# led_kocka_gornja.net
KiCad netlist of a schematic drawn in EAGLE
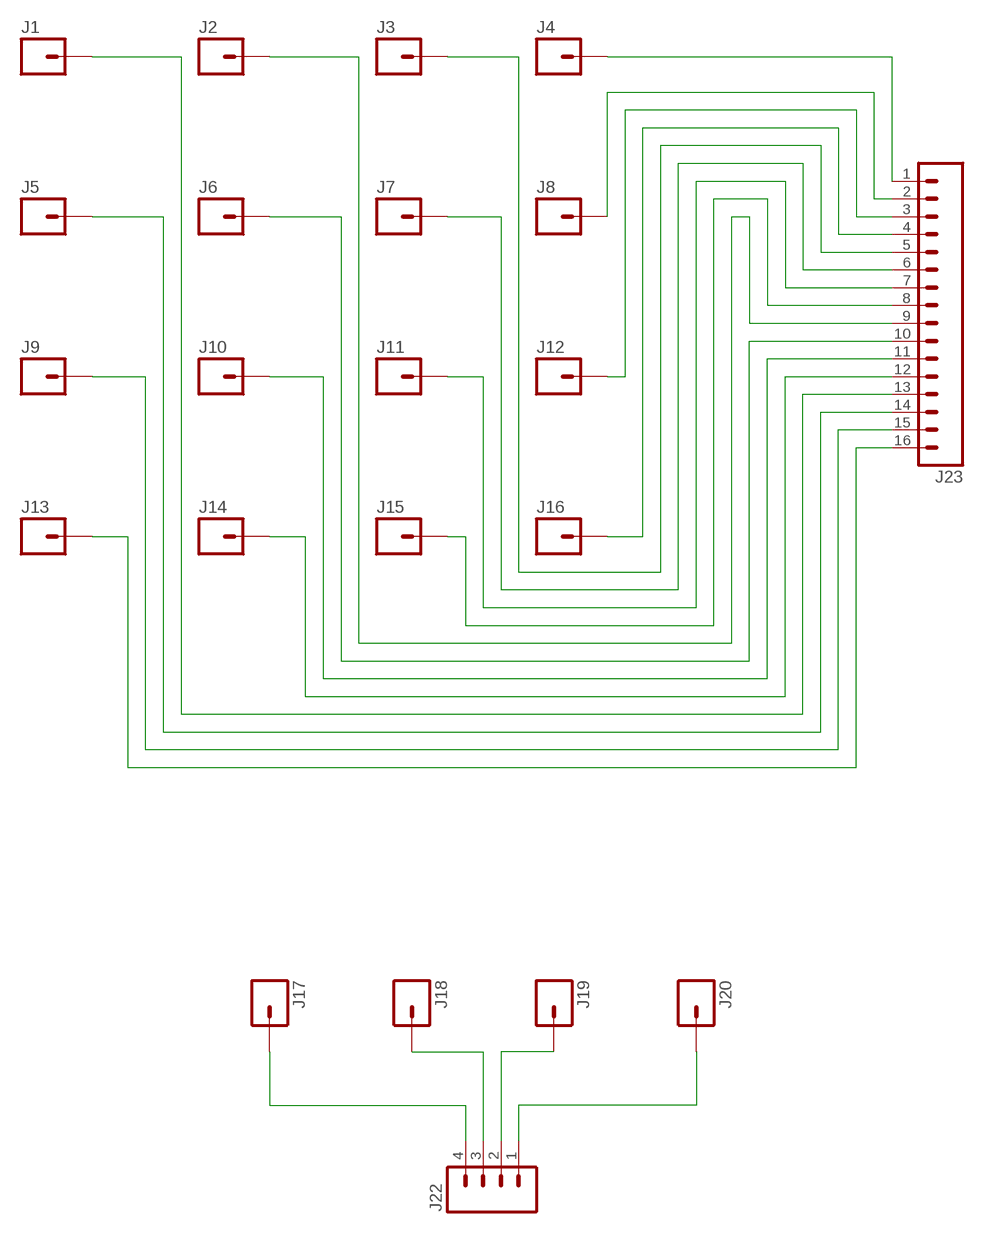
[diagram p0: schematic, sheet 1]

(export (version "E")
  (design (tool "Eeschema 10.0.6"))
  (components
    (comp (ref "J1")
      (value "M01NOSILK-KIT")
      (footprint "eagle-import:1X01NS-KIT")
      (libsource (lib "eagle-import") (part "M01NOSILK-KIT"))
    )
    (comp (ref "J2")
      (value "M01NOSILK-KIT")
      (footprint "eagle-import:1X01NS-KIT")
      (libsource (lib "eagle-import") (part "M01NOSILK-KIT"))
    )
    (comp (ref "J3")
      (value "M01NOSILK-KIT")
      (footprint "eagle-import:1X01NS-KIT")
      (libsource (lib "eagle-import") (part "M01NOSILK-KIT"))
    )
    (comp (ref "J4")
      (value "M01NOSILK-KIT")
      (footprint "eagle-import:1X01NS-KIT")
      (libsource (lib "eagle-import") (part "M01NOSILK-KIT"))
    )
    (comp (ref "J5")
      (value "M01NOSILK-KIT")
      (footprint "eagle-import:1X01NS-KIT")
      (libsource (lib "eagle-import") (part "M01NOSILK-KIT"))
    )
    (comp (ref "J6")
      (value "M01NOSILK-KIT")
      (footprint "eagle-import:1X01NS-KIT")
      (libsource (lib "eagle-import") (part "M01NOSILK-KIT"))
    )
    (comp (ref "J7")
      (value "M01NOSILK-KIT")
      (footprint "eagle-import:1X01NS-KIT")
      (libsource (lib "eagle-import") (part "M01NOSILK-KIT"))
    )
    (comp (ref "J8")
      (value "M01NOSILK-KIT")
      (footprint "eagle-import:1X01NS-KIT")
      (libsource (lib "eagle-import") (part "M01NOSILK-KIT"))
    )
    (comp (ref "J9")
      (value "M01NOSILK-KIT")
      (footprint "eagle-import:1X01NS-KIT")
      (libsource (lib "eagle-import") (part "M01NOSILK-KIT"))
    )
    (comp (ref "J10")
      (value "M01NOSILK-KIT")
      (footprint "eagle-import:1X01NS-KIT")
      (libsource (lib "eagle-import") (part "M01NOSILK-KIT"))
    )
    (comp (ref "J11")
      (value "M01NOSILK-KIT")
      (footprint "eagle-import:1X01NS-KIT")
      (libsource (lib "eagle-import") (part "M01NOSILK-KIT"))
    )
    (comp (ref "J12")
      (value "M01NOSILK-KIT")
      (footprint "eagle-import:1X01NS-KIT")
      (libsource (lib "eagle-import") (part "M01NOSILK-KIT"))
    )
    (comp (ref "J13")
      (value "M01NOSILK-KIT")
      (footprint "eagle-import:1X01NS-KIT")
      (libsource (lib "eagle-import") (part "M01NOSILK-KIT"))
    )
    (comp (ref "J14")
      (value "M01NOSILK-KIT")
      (footprint "eagle-import:1X01NS-KIT")
      (libsource (lib "eagle-import") (part "M01NOSILK-KIT"))
    )
    (comp (ref "J15")
      (value "M01NOSILK-KIT")
      (footprint "eagle-import:1X01NS-KIT")
      (libsource (lib "eagle-import") (part "M01NOSILK-KIT"))
    )
    (comp (ref "J16")
      (value "M01NOSILK-KIT")
      (footprint "eagle-import:1X01NS-KIT")
      (libsource (lib "eagle-import") (part "M01NOSILK-KIT"))
    )
    (comp (ref "J17")
      (value "M01NOSILK-KIT")
      (footprint "eagle-import:1X01NS-KIT")
      (libsource (lib "eagle-import") (part "M01NOSILK-KIT"))
    )
    (comp (ref "J18")
      (value "M01NOSILK-KIT")
      (footprint "eagle-import:1X01NS-KIT")
      (libsource (lib "eagle-import") (part "M01NOSILK-KIT"))
    )
    (comp (ref "J19")
      (value "M01NOSILK-KIT")
      (footprint "eagle-import:1X01NS-KIT")
      (libsource (lib "eagle-import") (part "M01NOSILK-KIT"))
    )
    (comp (ref "J20")
      (value "M01NOSILK-KIT")
      (footprint "eagle-import:1X01NS-KIT")
      (libsource (lib "eagle-import") (part "M01NOSILK-KIT"))
    )
    (comp (ref "J22")
      (value "M04LONGPADS")
      (footprint "eagle-import:1X04_LONGPADS")
      (libsource (lib "eagle-import") (part "M04LONGPADS"))
    )
    (comp (ref "J23")
      (value "M16LONGPADS")
      (footprint "eagle-import:1X16_LONGPADS")
      (libsource (lib "eagle-import") (part "M16LONGPADS"))
    )
  )
  (nets
    (net (code "1") (name "Net-(J1-Pad1)") (class "Default")
      (node (ref "J1") (pin "1") (pinfunction "1_1") (pintype "passive"))
      (node (ref "J23") (pin "13") (pinfunction "13_13") (pintype "passive"))
    )
    (net (code "2") (name "Net-(J2-Pad1)") (class "Default")
      (node (ref "J2") (pin "1") (pinfunction "1_1") (pintype "passive"))
      (node (ref "J23") (pin "9") (pinfunction "9_9") (pintype "passive"))
    )
    (net (code "3") (name "Net-(J10-Pad1)") (class "Default")
      (node (ref "J10") (pin "1") (pinfunction "1_1") (pintype "passive"))
      (node (ref "J23") (pin "11") (pinfunction "11_11") (pintype "passive"))
    )
    (net (code "4") (name "Net-(J11-Pad1)") (class "Default")
      (node (ref "J11") (pin "1") (pinfunction "1_1") (pintype "passive"))
      (node (ref "J23") (pin "7") (pinfunction "7_7") (pintype "passive"))
    )
    (net (code "5") (name "Net-(J12-Pad1)") (class "Default")
      (node (ref "J12") (pin "1") (pinfunction "1_1") (pintype "passive"))
      (node (ref "J23") (pin "3") (pinfunction "3_3") (pintype "passive"))
    )
    (net (code "6") (name "Net-(J13-Pad1)") (class "Default")
      (node (ref "J13") (pin "1") (pinfunction "1_1") (pintype "passive"))
      (node (ref "J23") (pin "16") (pinfunction "16_16") (pintype "passive"))
    )
    (net (code "7") (name "Net-(J14-Pad1)") (class "Default")
      (node (ref "J14") (pin "1") (pinfunction "1_1") (pintype "passive"))
      (node (ref "J23") (pin "12") (pinfunction "12_12") (pintype "passive"))
    )
    (net (code "8") (name "Net-(J15-Pad1)") (class "Default")
      (node (ref "J15") (pin "1") (pinfunction "1_1") (pintype "passive"))
      (node (ref "J23") (pin "8") (pinfunction "8_8") (pintype "passive"))
    )
    (net (code "9") (name "Net-(J16-Pad1)") (class "Default")
      (node (ref "J16") (pin "1") (pinfunction "1_1") (pintype "passive"))
      (node (ref "J23") (pin "4") (pinfunction "4_4") (pintype "passive"))
    )
    (net (code "10") (name "Net-(J17-Pad1)") (class "Default")
      (node (ref "J17") (pin "1") (pinfunction "1_1") (pintype "passive"))
      (node (ref "J22") (pin "4") (pinfunction "4_4") (pintype "passive"))
    )
    (net (code "11") (name "Net-(J18-Pad1)") (class "Default")
      (node (ref "J18") (pin "1") (pinfunction "1_1") (pintype "passive"))
      (node (ref "J22") (pin "3") (pinfunction "3_3") (pintype "passive"))
    )
    (net (code "12") (name "Net-(J19-Pad1)") (class "Default")
      (node (ref "J19") (pin "1") (pinfunction "1_1") (pintype "passive"))
      (node (ref "J22") (pin "2") (pinfunction "2_2") (pintype "passive"))
    )
    (net (code "13") (name "Net-(J20-Pad1)") (class "Default")
      (node (ref "J20") (pin "1") (pinfunction "1_1") (pintype "passive"))
      (node (ref "J22") (pin "1") (pinfunction "1_1") (pintype "passive"))
    )
    (net (code "14") (name "Net-(J23-Pad1)") (class "Default")
      (node (ref "J23") (pin "1") (pinfunction "1_1") (pintype "passive"))
      (node (ref "J4") (pin "1") (pinfunction "1_1") (pintype "passive"))
    )
    (net (code "15") (name "Net-(J23-Pad2)") (class "Default")
      (node (ref "J23") (pin "2") (pinfunction "2_2") (pintype "passive"))
      (node (ref "J8") (pin "1") (pinfunction "1_1") (pintype "passive"))
    )
    (net (code "16") (name "Net-(J23-Pad5)") (class "Default")
      (node (ref "J23") (pin "5") (pinfunction "5_5") (pintype "passive"))
      (node (ref "J3") (pin "1") (pinfunction "1_1") (pintype "passive"))
    )
    (net (code "17") (name "Net-(J23-Pad6)") (class "Default")
      (node (ref "J23") (pin "6") (pinfunction "6_6") (pintype "passive"))
      (node (ref "J7") (pin "1") (pinfunction "1_1") (pintype "passive"))
    )
    (net (code "18") (name "Net-(J23-Pad10)") (class "Default")
      (node (ref "J23") (pin "10") (pinfunction "10_10") (pintype "passive"))
      (node (ref "J6") (pin "1") (pinfunction "1_1") (pintype "passive"))
    )
    (net (code "19") (name "Net-(J23-Pad14)") (class "Default")
      (node (ref "J23") (pin "14") (pinfunction "14_14") (pintype "passive"))
      (node (ref "J5") (pin "1") (pinfunction "1_1") (pintype "passive"))
    )
    (net (code "20") (name "Net-(J23-Pad15)") (class "Default")
      (node (ref "J23") (pin "15") (pinfunction "15_15") (pintype "passive"))
      (node (ref "J9") (pin "1") (pinfunction "1_1") (pintype "passive"))
    )
  )
)
